# MaUWB.net
KiCad netlist of a schematic drawn in Altium Designer
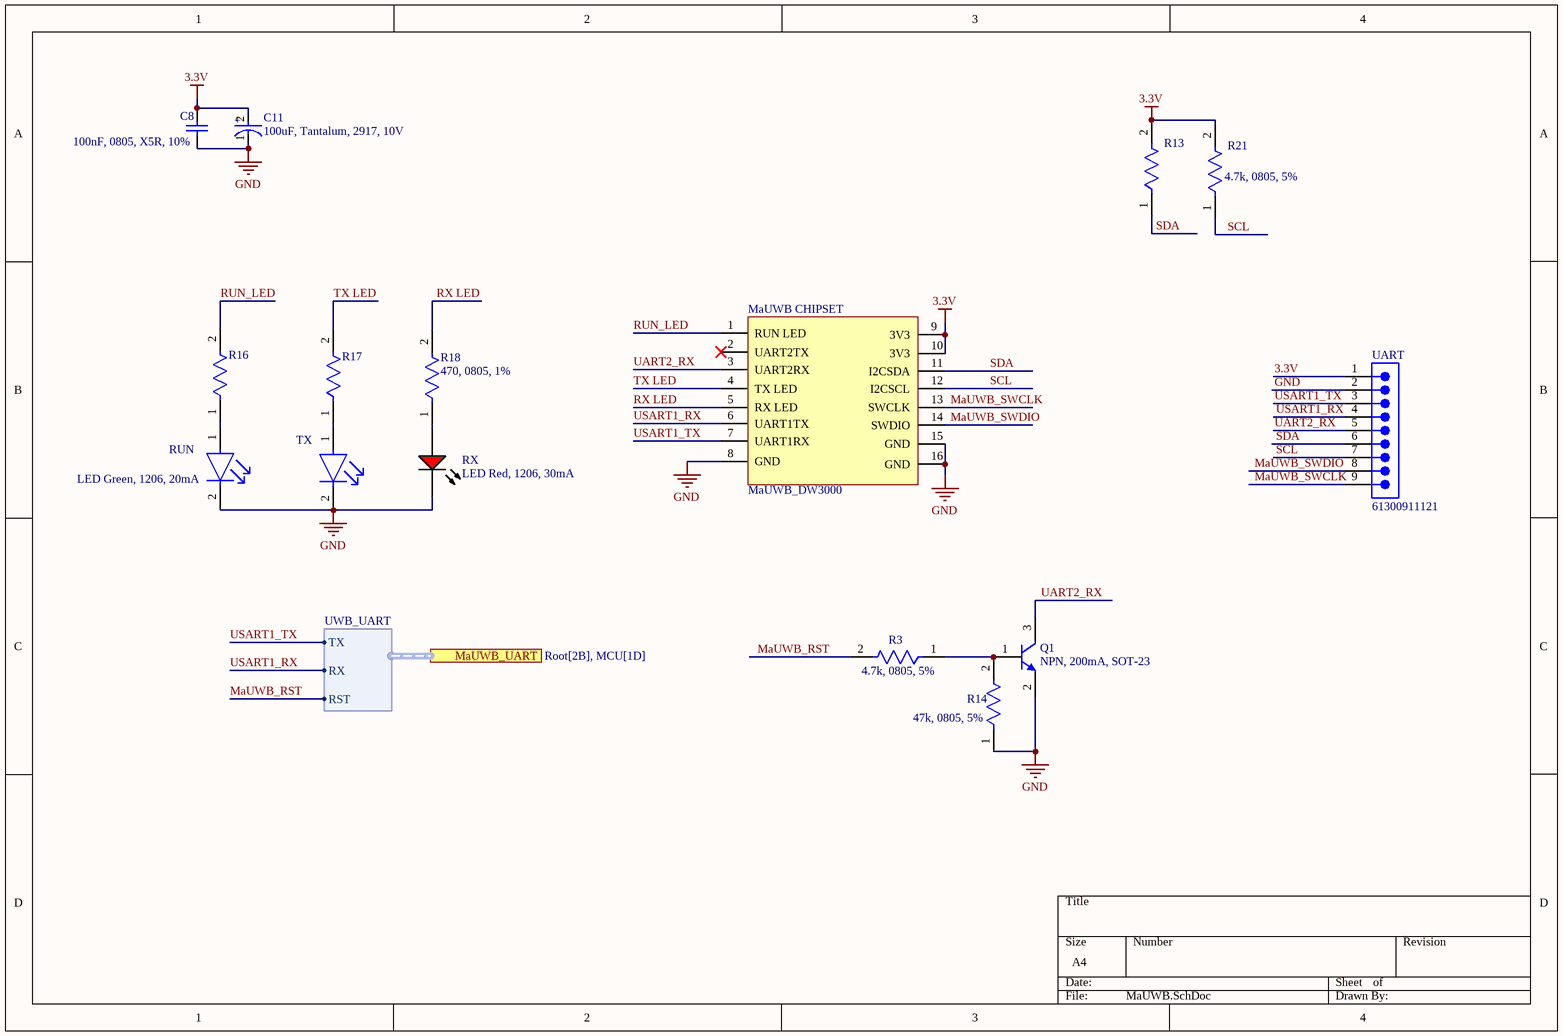
[diagram p0: MaUWB.SchDoc]

(export (version "E")
  (design (tool "Eeschema 10.0.6"))
  (components
    (comp (ref "C8")
      (value "100nF, 0805, X5R, 10%")
      (footprint "CAPC2013X140X50ML20T25")
      (fields
        (field (name "PART NUMBER") "08055D104KAT2A")
        (field (name "MANUFACTURER") "AVX Interconnect / Elco")
      )
      (libsource (lib "Altium Content Vault") (part "CAP"))
    )
    (comp (ref "C11")
      (value "100uF, Tantalum, 2917, 10V")
      (footprint "FP-TAJD-MFG")
      (description "100uF 10V  ±10% 900mΩ 2917  SMD Tantalum Capacitor")
      (fields (field (name "TOLERANCE") "10%") (field (name "VOLTAGE") "10V"))
      (libsource (lib "Altium Content Vault") (part "a00bbbee19879c290e62620ae7e47b1"))
    )
    (comp (ref "MaUWB CHIPSET")
      (value "MaUWB_DW3000")
      (footprint "MaUWB_DW3000:MaUWB_DW3000")
      (libsource (lib "MaUWB_DW3000") (part "MaUWB_DW3000"))
    )
    (comp (ref "Q1")
      (value "NPN, 200mA, SOT-23")
      (footprint "ONSC-SOT-23-3-318-08_V")
      (description "General Purpose Transistor, NPN Silicon, 3-Pin SOT-23, Pb-Free, Tape and Reel")
      (fields (field (name "MANUFACTURER") "On Semiconductor") (field (name "PARTNUMBER") "MMBT3904LT1G"))
      (libsource (lib "Altium Content Vault") (part "ONSC-NPN-B1E2C3-3"))
    )
    (comp (ref "R3")
      (value "4.7k, 0805, 5%")
      (footprint "FP-RMCF0805-MFG")
      (description "4.7kΩ ±5% 0.125W 0805 Thick Film Chip Resistor AEC-Q200 compliant")
      (fields (field (name "TOLERANCE") "5%"))
      (libsource (lib "Altium Content Vault") (part "1029c3af85768c4190bb7ad29bc67b5"))
    )
    (comp (ref "R13")
      (value "~")
      (footprint "FP-RMCF0805-MFG")
      (description "4.7kΩ ±5% 0.125W 0805 Thick Film Chip Resistor AEC-Q200 compliant")
      (fields (field (name "TOLERANCE") "5%"))
      (libsource (lib "Altium Content Vault") (part "1029c3af85768c4190bb7ad29bc67b5"))
    )
    (comp (ref "R14")
      (value "47k, 0805, 5%")
      (footprint "FP-CRGCQ0805-IPC_C")
      (description "CRGCQ0805 47KΩ 0.125W ±100ppm/°C 5% 150V")
      (fields
        (field (name "OCTOPART") "https://octopart.com/crgcq0805j47k-te+connectivity-91018230")
        (field (name "TOLERANCE") "0.05")
      )
      (libsource (lib "Altium Content Vault") (part "1029c3af85768c4190bb7ad29bc67b5"))
    )
    (comp (ref "R16")
      (value "~")
      (footprint "FP-RMCF0805-IPC_C")
      (description "470Ω ±1% 0.125W 0805 Thick Film Chip Resistor AEC-Q200 compliant")
      (fields (field (name "TOLERANCE") "1%"))
      (libsource (lib "Altium Content Vault") (part "1029c3af85768c4190bb7ad29bc67b5"))
    )
    (comp (ref "R17")
      (value "~")
      (footprint "FP-RMCF0805-IPC_C")
      (description "470Ω ±1% 0.125W 0805 Thick Film Chip Resistor AEC-Q200 compliant")
      (fields (field (name "TOLERANCE") "1%"))
      (libsource (lib "Altium Content Vault") (part "1029c3af85768c4190bb7ad29bc67b5"))
    )
    (comp (ref "R18")
      (value "470, 0805, 1%")
      (footprint "FP-RMCF0805-IPC_C")
      (description "470Ω ±1% 0.125W 0805 Thick Film Chip Resistor AEC-Q200 compliant")
      (fields (field (name "TOLERANCE") "1%"))
      (libsource (lib "Altium Content Vault") (part "1029c3af85768c4190bb7ad29bc67b5"))
    )
    (comp (ref "R21")
      (value "4.7k, 0805, 5%")
      (footprint "FP-RMCF0805-MFG")
      (description "4.7kΩ ±5% 0.125W 0805 Thick Film Chip Resistor AEC-Q200 compliant")
      (fields (field (name "TOLERANCE") "5%"))
      (libsource (lib "Altium Content Vault") (part "1029c3af85768c4190bb7ad29bc67b5"))
    )
    (comp (ref "RUN")
      (value "LED Green, 1206, 20mA")
      (footprint "FP-SML-LX1206GC-TR-MFG")
      (description "LED GREEN CLEAR 1206 SMD")
      (libsource (lib "Altium Content Vault") (part "ab1c01a81903e929fc6c44469aada92"))
    )
    (comp (ref "RX")
      (value "LED Red, 1206, 30mA")
      (footprint "LUMX-SML-LX1206IC_V")
      (description "LED Red, 65 mW, -40 to 85 degC, 2-Pin SMD, RoHS, Tape and Reel")
      (fields (field (name "MANUFACTURER") "Lumex") (field (name "PART NO") "SML-LX1206IC-TR"))
      (libsource (lib "Altium Content Vault") (part "LED-RED-AK-2"))
    )
    (comp (ref "TX")
      (value "~")
      (footprint "FP-SML-LX1206GC-TR-MFG")
      (description "LED GREEN CLEAR 1206 SMD")
      (libsource (lib "Altium Content Vault") (part "ab1c01a81903e929fc6c44469aada92"))
    )
    (comp (ref "UART")
      (value "61300911121")
      (footprint "61300911121")
      (description "THT Vertical Pin Header WR-PHD, Pitch 2.54 mm, Single Row, 9 pins")
      (libsource (lib "Altium Content Vault") (part "Header_Male_1R_09P"))
    )
  )
  (nets
    (net (code "2") (name "/MaUWB_RST") (class "Default")
      (node (ref "R3") (pin "2") (pinfunction "2_2") (pintype "passive"))
    )
    (net (code "3") (name "/MaUWB_SWCLK") (class "Default")
      (node (ref "MaUWB CHIPSET") (pin "13") (pinfunction "SWCLK_13") (pintype "passive"))
      (node (ref "UART") (pin "9") (pinfunction "9_9") (pintype "passive"))
    )
    (net (code "4") (name "/MaUWB_SWDIO") (class "Default")
      (node (ref "MaUWB CHIPSET") (pin "14") (pinfunction "SWDIO_14") (pintype "passive"))
      (node (ref "UART") (pin "8") (pinfunction "8_8") (pintype "passive"))
    )
    (net (code "5") (name "/RUN_LED") (class "Default")
      (node (ref "MaUWB CHIPSET") (pin "1") (pinfunction "RUN_LED_1") (pintype "passive"))
      (node (ref "R16") (pin "2") (pinfunction "2_2") (pintype "passive"))
    )
    (net (code "6") (name "/RX LED") (class "Default")
      (node (ref "MaUWB CHIPSET") (pin "5") (pinfunction "RX_LED_5") (pintype "passive"))
      (node (ref "R18") (pin "2") (pinfunction "2_2") (pintype "passive"))
    )
    (net (code "7") (name "/SCL") (class "Default")
      (node (ref "MaUWB CHIPSET") (pin "12") (pinfunction "I2CSCL_12") (pintype "passive"))
      (node (ref "R21") (pin "1") (pinfunction "1_1") (pintype "passive"))
      (node (ref "UART") (pin "7") (pinfunction "7_7") (pintype "passive"))
    )
    (net (code "8") (name "/SDA") (class "Default")
      (node (ref "MaUWB CHIPSET") (pin "11") (pinfunction "I2CSDA_11") (pintype "passive"))
      (node (ref "R13") (pin "1") (pinfunction "1_1") (pintype "passive"))
      (node (ref "UART") (pin "6") (pinfunction "6_6") (pintype "passive"))
    )
    (net (code "9") (name "/TX LED") (class "Default")
      (node (ref "MaUWB CHIPSET") (pin "4") (pinfunction "TX_LED_4") (pintype "passive"))
      (node (ref "R17") (pin "2") (pinfunction "2_2") (pintype "passive"))
    )
    (net (code "10") (name "/UART2_RX") (class "Default")
      (node (ref "MaUWB CHIPSET") (pin "3") (pinfunction "UART2RX_3") (pintype "passive"))
      (node (ref "Q1") (pin "3") (pinfunction "C_3") (pintype "passive"))
      (node (ref "UART") (pin "5") (pinfunction "5_5") (pintype "passive"))
    )
    (net (code "11") (name "/USART1_RX") (class "Default")
      (node (ref "MaUWB CHIPSET") (pin "6") (pinfunction "UART1TX_6") (pintype "passive"))
      (node (ref "UART") (pin "4") (pinfunction "4_4") (pintype "passive"))
    )
    (net (code "12") (name "/USART1_TX") (class "Default")
      (node (ref "MaUWB CHIPSET") (pin "7") (pinfunction "UART1RX_7") (pintype "passive"))
      (node (ref "UART") (pin "3") (pinfunction "3_3") (pintype "passive"))
    )
    (net (code "14") (name "3.3V") (class "Default")
      (node (ref "C11") (pin "2") (pinfunction "A_2") (pintype "passive"))
      (node (ref "C8") (pin "2") (pinfunction "2_2") (pintype "passive"))
      (node (ref "MaUWB CHIPSET") (pin "10") (pinfunction "3V3_10") (pintype "passive"))
      (node (ref "MaUWB CHIPSET") (pin "9") (pinfunction "3V3_9") (pintype "passive"))
      (node (ref "R13") (pin "2") (pinfunction "2_2") (pintype "passive"))
      (node (ref "R21") (pin "2") (pinfunction "2_2") (pintype "passive"))
      (node (ref "UART") (pin "1") (pinfunction "1_1") (pintype "passive"))
    )
    (net (code "15") (name "GND") (class "Default")
      (node (ref "C11") (pin "1") (pinfunction "C_1") (pintype "passive"))
      (node (ref "C8") (pin "1") (pinfunction "1_1") (pintype "passive"))
      (node (ref "MaUWB CHIPSET") (pin "15") (pinfunction "GND_15") (pintype "passive"))
      (node (ref "MaUWB CHIPSET") (pin "16") (pinfunction "GND_16") (pintype "passive"))
      (node (ref "MaUWB CHIPSET") (pin "8") (pinfunction "GND_8") (pintype "passive"))
      (node (ref "Q1") (pin "2") (pinfunction "E_2") (pintype "passive"))
      (node (ref "R14") (pin "1") (pinfunction "1_1") (pintype "passive"))
      (node (ref "RUN") (pin "2") (pinfunction "C_2") (pintype "passive"))
      (node (ref "RX") (pin "2") (pinfunction "K_2") (pintype "passive"))
      (node (ref "TX") (pin "2") (pinfunction "C_2") (pintype "passive"))
      (node (ref "UART") (pin "2") (pinfunction "2_2") (pintype "passive"))
    )
    (net (code "16") (name "Net-(Q1-B)") (class "Default")
      (node (ref "Q1") (pin "1") (pinfunction "B_1") (pintype "passive"))
      (node (ref "R14") (pin "2") (pinfunction "2_2") (pintype "passive"))
      (node (ref "R3") (pin "1") (pinfunction "1_1") (pintype "passive"))
    )
    (net (code "17") (name "Net-(RUN-A)") (class "Default")
      (node (ref "R16") (pin "1") (pinfunction "1_1") (pintype "passive"))
      (node (ref "RUN") (pin "1") (pinfunction "A_1") (pintype "passive"))
    )
    (net (code "18") (name "Net-(RX-A)") (class "Default")
      (node (ref "R18") (pin "1") (pinfunction "1_1") (pintype "passive"))
      (node (ref "RX") (pin "1") (pinfunction "A_1") (pintype "passive"))
    )
    (net (code "19") (name "Net-(TX-A)") (class "Default")
      (node (ref "R17") (pin "1") (pinfunction "1_1") (pintype "passive"))
      (node (ref "TX") (pin "1") (pinfunction "A_1") (pintype "passive"))
    )
    (net (code "20") (name "unconnected-(MaUWB CHIPSET-UART2TX-Pad2)") (class "Default")
      (node (ref "MaUWB CHIPSET") (pin "2") (pinfunction "UART2TX_2") (pintype "passive+no_connect"))
    )
  )
)
